# Propulsion.net
KiCad netlist of a schematic drawn in Altium Designer
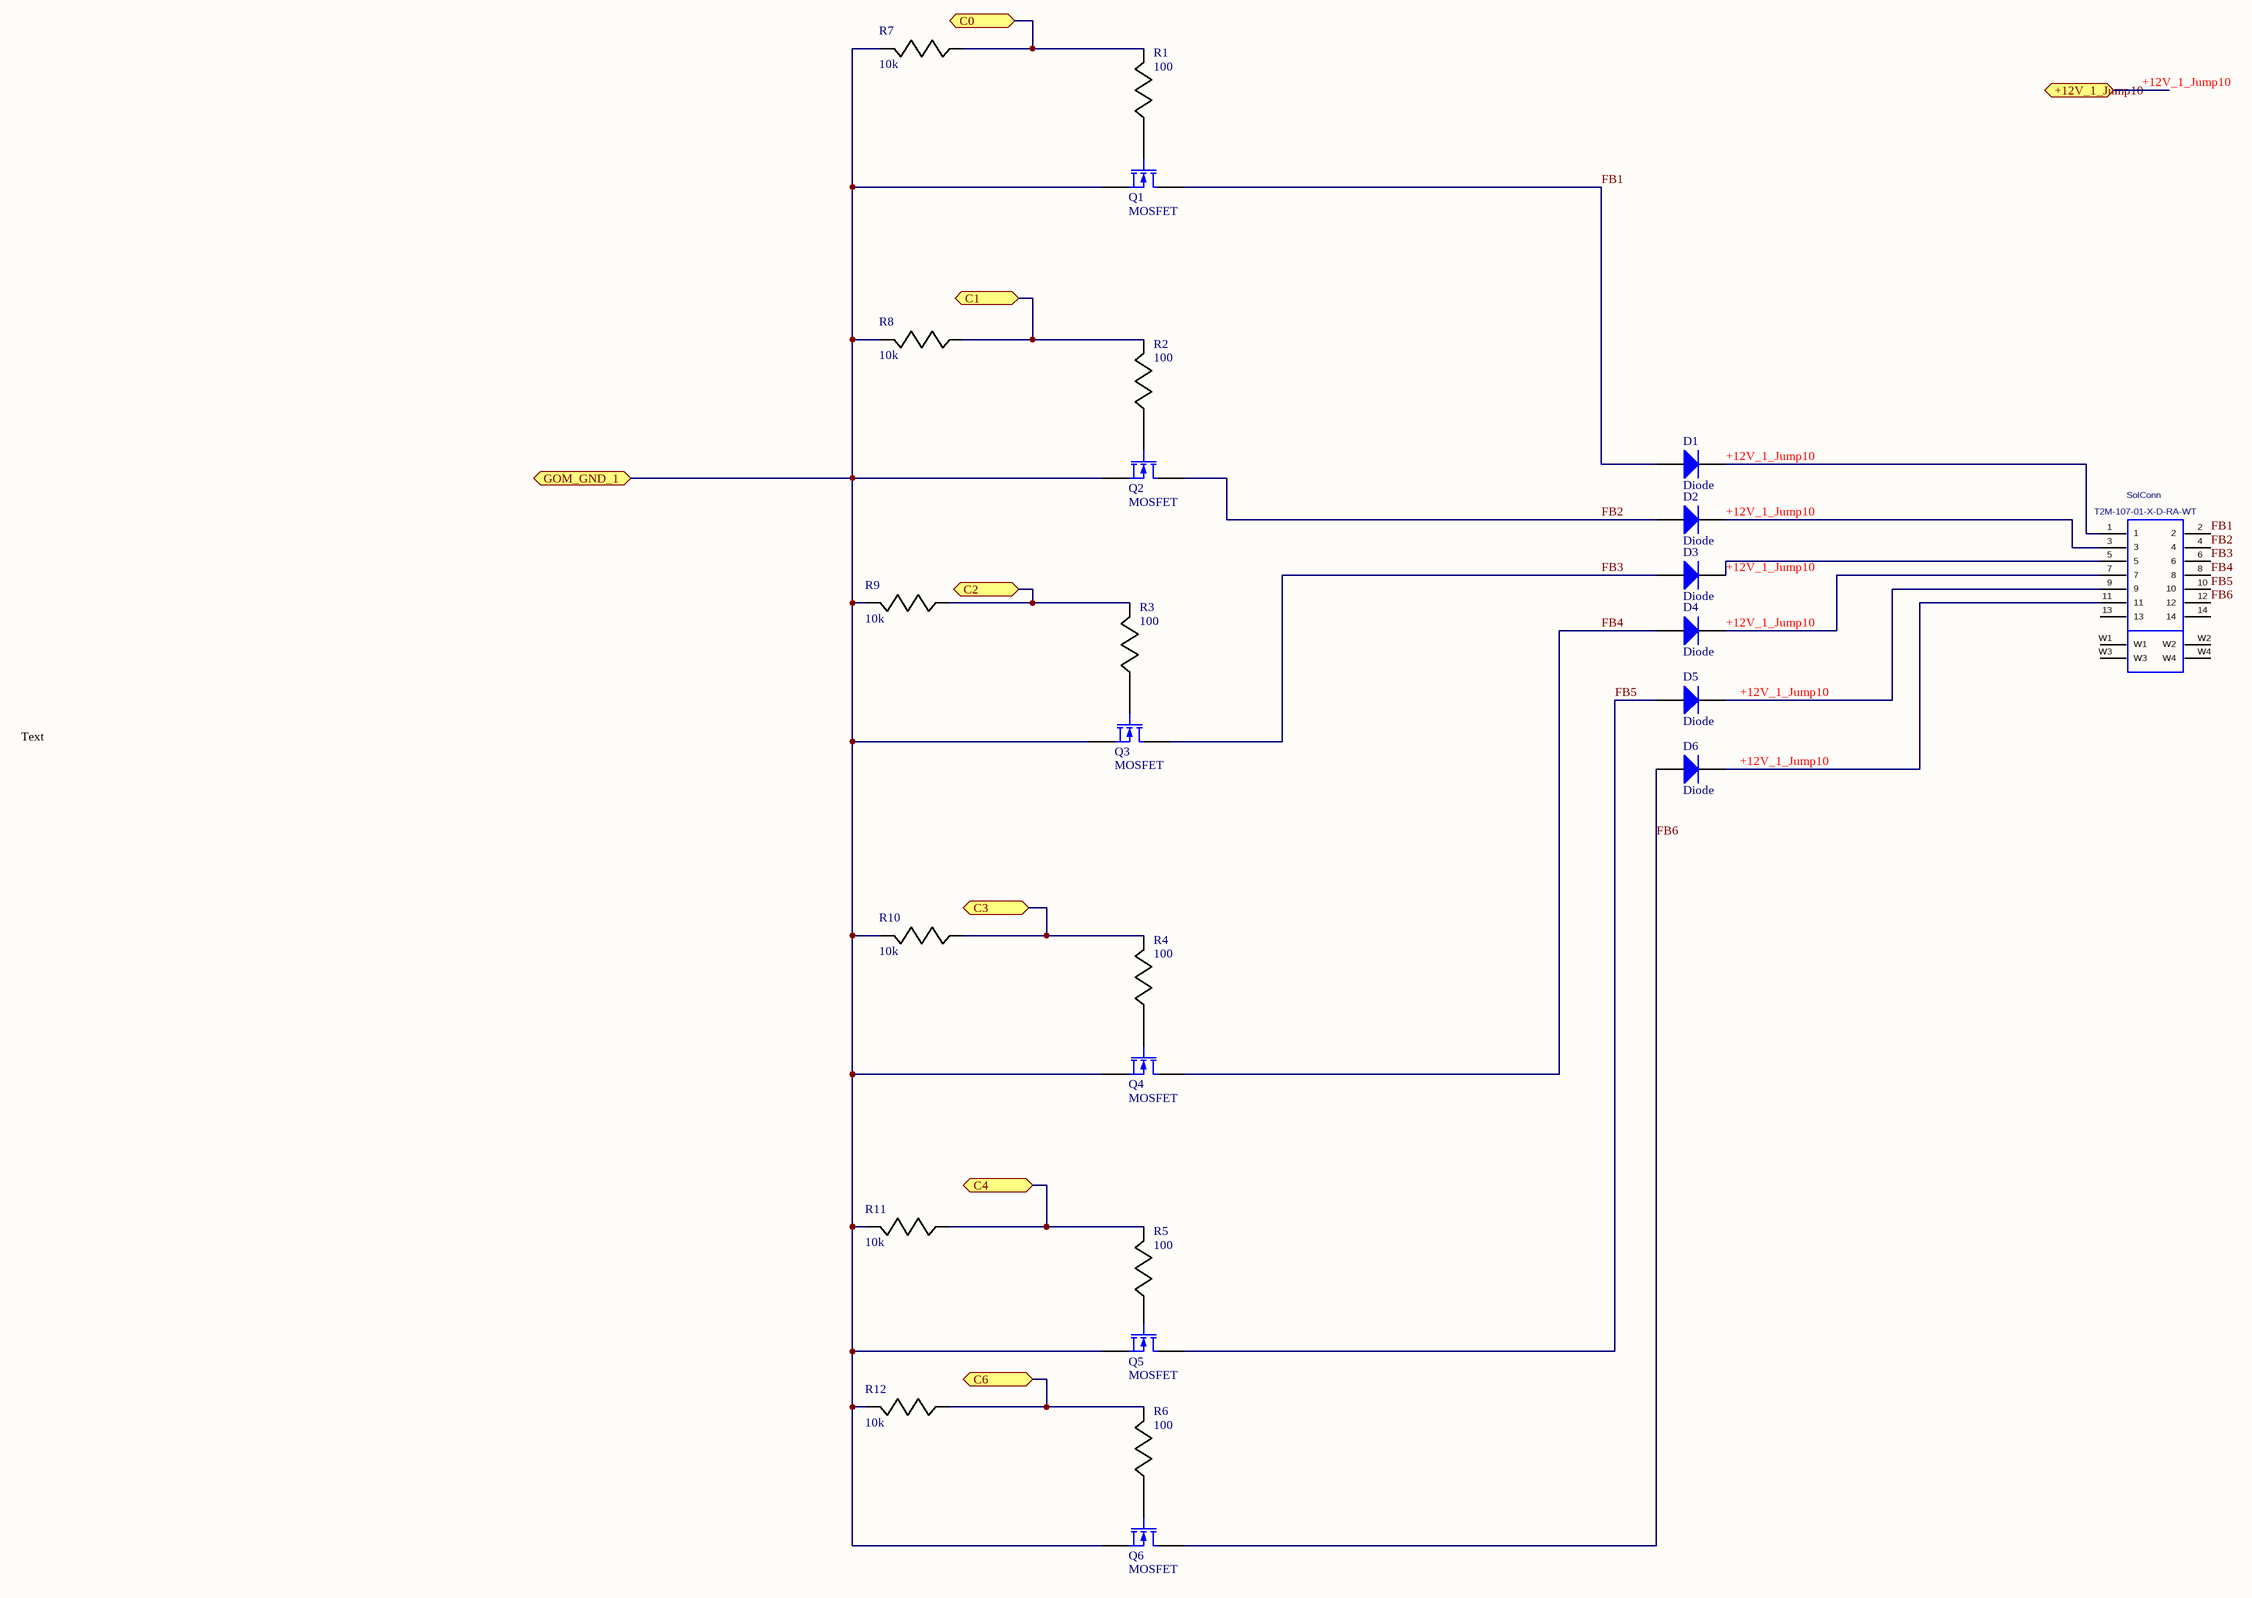
[diagram p0: Propulsion.SchDoc]

(export (version "E")
  (design (tool "Eeschema 10.0.6"))
  (components
    (comp (ref "D1")
      (value "Diode")
      (footprint "SMC")
      (description "Default Diode")
      (fields (field (name "PUBLISHER") "Altium Limited"))
      (libsource (lib "Miscellaneous Devices") (part "Diode"))
    )
    (comp (ref "D2")
      (value "Diode")
      (footprint "SMC")
      (description "Default Diode")
      (fields (field (name "PUBLISHER") "Altium Limited"))
      (libsource (lib "Miscellaneous Devices") (part "Diode"))
    )
    (comp (ref "D3")
      (value "Diode")
      (footprint "SMC")
      (description "Default Diode")
      (fields (field (name "PUBLISHER") "Altium Limited"))
      (libsource (lib "Miscellaneous Devices") (part "Diode"))
    )
    (comp (ref "D4")
      (value "Diode")
      (footprint "SMC")
      (description "Default Diode")
      (fields (field (name "PUBLISHER") "Altium Limited"))
      (libsource (lib "Miscellaneous Devices") (part "Diode"))
    )
    (comp (ref "D5")
      (value "Diode")
      (footprint "SMC")
      (description "Default Diode")
      (fields (field (name "PUBLISHER") "Altium Limited"))
      (libsource (lib "Miscellaneous Devices") (part "Diode"))
    )
    (comp (ref "D6")
      (value "Diode")
      (footprint "SMC")
      (description "Default Diode")
      (fields (field (name "PUBLISHER") "Altium Limited"))
      (libsource (lib "Miscellaneous Devices") (part "Diode"))
    )
    (comp (ref "Q1")
      (value "MOSFET")
      (footprint "TO-226-AA")
      (description "N-Channel MOSFET")
      (fields (field (name "PUBLISHER") "Altium Limited"))
      (libsource (lib "Miscellaneous Devices") (part "MOSFET-N"))
    )
    (comp (ref "Q2")
      (value "MOSFET")
      (footprint "TO-226-AA")
      (description "N-Channel MOSFET")
      (fields (field (name "PUBLISHER") "Altium Limited"))
      (libsource (lib "Miscellaneous Devices") (part "MOSFET-N"))
    )
    (comp (ref "Q3")
      (value "MOSFET")
      (footprint "TO-226-AA")
      (description "N-Channel MOSFET")
      (fields (field (name "PUBLISHER") "Altium Limited"))
      (libsource (lib "Miscellaneous Devices") (part "MOSFET-N"))
    )
    (comp (ref "Q4")
      (value "MOSFET")
      (footprint "TO-226-AA")
      (description "N-Channel MOSFET")
      (fields (field (name "PUBLISHER") "Altium Limited"))
      (libsource (lib "Miscellaneous Devices") (part "MOSFET-N"))
    )
    (comp (ref "Q5")
      (value "MOSFET")
      (footprint "TO-226-AA")
      (description "N-Channel MOSFET")
      (fields (field (name "PUBLISHER") "Altium Limited"))
      (libsource (lib "Miscellaneous Devices") (part "MOSFET-N"))
    )
    (comp (ref "Q6")
      (value "MOSFET")
      (footprint "TO-226-AA")
      (description "N-Channel MOSFET")
      (fields (field (name "PUBLISHER") "Altium Limited"))
      (libsource (lib "Miscellaneous Devices") (part "MOSFET-N"))
    )
    (comp (ref "R1")
      (value "100")
      (footprint "AXIAL-0.3")
      (description "Imported")
      (fields (field (name "MANUFACTURER_PART_NUMBER") "PMR100HZPFU6L00"))
      (libsource (lib "2016-03-26_18-23-46") (part "PMR100HZPFU6L00"))
    )
    (comp (ref "R2")
      (value "100")
      (footprint "AXIAL-0.3")
      (description "Imported")
      (fields (field (name "MANUFACTURER_PART_NUMBER") "PMR100HZPFU6L00"))
      (libsource (lib "2016-03-26_18-23-46") (part "PMR100HZPFU6L00"))
    )
    (comp (ref "R3")
      (value "100")
      (footprint "AXIAL-0.3")
      (description "Imported")
      (fields (field (name "MANUFACTURER_PART_NUMBER") "PMR100HZPFU6L00"))
      (libsource (lib "2016-03-26_18-23-46") (part "PMR100HZPFU6L00"))
    )
    (comp (ref "R4")
      (value "100")
      (footprint "AXIAL-0.3")
      (description "Imported")
      (fields (field (name "MANUFACTURER_PART_NUMBER") "PMR100HZPFU6L00"))
      (libsource (lib "2016-03-26_18-23-46") (part "PMR100HZPFU6L00"))
    )
    (comp (ref "R5")
      (value "100")
      (footprint "AXIAL-0.3")
      (description "Imported")
      (fields (field (name "MANUFACTURER_PART_NUMBER") "PMR100HZPFU6L00"))
      (libsource (lib "2016-03-26_18-23-46") (part "PMR100HZPFU6L00"))
    )
    (comp (ref "R6")
      (value "100")
      (footprint "AXIAL-0.3")
      (description "Imported")
      (fields (field (name "MANUFACTURER_PART_NUMBER") "PMR100HZPFU6L00"))
      (libsource (lib "2016-03-26_18-23-46") (part "PMR100HZPFU6L00"))
    )
    (comp (ref "R7")
      (value "10k")
      (footprint "AXIAL-0.3")
      (description "Imported")
      (fields (field (name "MANUFACTURER_PART_NUMBER") "PMR100HZPFU6L00"))
      (libsource (lib "2016-03-26_18-23-46") (part "PMR100HZPFU6L00"))
    )
    (comp (ref "R8")
      (value "10k")
      (footprint "AXIAL-0.3")
      (description "Imported")
      (fields (field (name "MANUFACTURER_PART_NUMBER") "PMR100HZPFU6L00"))
      (libsource (lib "2016-03-26_18-23-46") (part "PMR100HZPFU6L00"))
    )
    (comp (ref "R9")
      (value "10k")
      (footprint "AXIAL-0.3")
      (description "Imported")
      (fields (field (name "MANUFACTURER_PART_NUMBER") "PMR100HZPFU6L00"))
      (libsource (lib "2016-03-26_18-23-46") (part "PMR100HZPFU6L00"))
    )
    (comp (ref "R10")
      (value "10k")
      (footprint "AXIAL-0.3")
      (description "Imported")
      (fields (field (name "MANUFACTURER_PART_NUMBER") "PMR100HZPFU6L00"))
      (libsource (lib "2016-03-26_18-23-46") (part "PMR100HZPFU6L00"))
    )
    (comp (ref "R11")
      (value "10k")
      (footprint "AXIAL-0.3")
      (description "Imported")
      (fields (field (name "MANUFACTURER_PART_NUMBER") "PMR100HZPFU6L00"))
      (libsource (lib "2016-03-26_18-23-46") (part "PMR100HZPFU6L00"))
    )
    (comp (ref "R12")
      (value "10k")
      (footprint "AXIAL-0.3")
      (description "Imported")
      (fields (field (name "MANUFACTURER_PART_NUMBER") "PMR100HZPFU6L00"))
      (libsource (lib "2016-03-26_18-23-46") (part "PMR100HZPFU6L00"))
    )
    (comp (ref "SolConn")
      (value "T2M-107-01-X-D-RA-WT")
      (footprint "T2M-107-01-X-D-RA-WT")
      (description "2MM PITCH SHROUDED RIGHT ANGLE TERMINAL STRIP.")
      (fields
        (field (name "MANUFACTURER") "SAMTEC")
        (field (name "CREATED") "September 24, 2014 - Wendy Xin")
      )
      (libsource (lib "T2M-107-01-X-D-RA-WT") (part "T2M-107-01-X-D-RA-WT"))
    )
  )
  (nets
    (net (code "1") (name "/+12V_1_Jump10") (class "Default")
      (node (ref "D1") (pin "2") (pinfunction "K_2") (pintype "passive"))
      (node (ref "D2") (pin "2") (pinfunction "K_2") (pintype "passive"))
      (node (ref "D3") (pin "2") (pinfunction "K_2") (pintype "passive"))
      (node (ref "D4") (pin "2") (pinfunction "K_2") (pintype "passive"))
      (node (ref "D5") (pin "2") (pinfunction "K_2") (pintype "passive"))
      (node (ref "D6") (pin "2") (pinfunction "K_2") (pintype "passive"))
      (node (ref "SolConn") (pin "1") (pinfunction "1_1") (pintype "passive"))
      (node (ref "SolConn") (pin "11") (pinfunction "11_11") (pintype "passive"))
      (node (ref "SolConn") (pin "3") (pinfunction "3_3") (pintype "passive"))
      (node (ref "SolConn") (pin "5") (pinfunction "5_5") (pintype "passive"))
      (node (ref "SolConn") (pin "7") (pinfunction "7_7") (pintype "passive"))
      (node (ref "SolConn") (pin "9") (pinfunction "9_9") (pintype "passive"))
    )
    (net (code "2") (name "/C0") (class "Default")
      (node (ref "R1") (pin "1") (pinfunction "1_1") (pintype "passive"))
      (node (ref "R7") (pin "2") (pinfunction "2_2") (pintype "passive"))
    )
    (net (code "3") (name "/C1") (class "Default")
      (node (ref "R2") (pin "1") (pinfunction "1_1") (pintype "passive"))
      (node (ref "R8") (pin "2") (pinfunction "2_2") (pintype "passive"))
    )
    (net (code "4") (name "/C2") (class "Default")
      (node (ref "R3") (pin "1") (pinfunction "1_1") (pintype "passive"))
      (node (ref "R9") (pin "2") (pinfunction "2_2") (pintype "passive"))
    )
    (net (code "5") (name "/C3") (class "Default")
      (node (ref "R10") (pin "2") (pinfunction "2_2") (pintype "passive"))
      (node (ref "R4") (pin "1") (pinfunction "1_1") (pintype "passive"))
    )
    (net (code "6") (name "/C4") (class "Default")
      (node (ref "R11") (pin "2") (pinfunction "2_2") (pintype "passive"))
      (node (ref "R5") (pin "1") (pinfunction "1_1") (pintype "passive"))
    )
    (net (code "7") (name "/C6") (class "Default")
      (node (ref "R12") (pin "2") (pinfunction "2_2") (pintype "passive"))
      (node (ref "R6") (pin "1") (pinfunction "1_1") (pintype "passive"))
    )
    (net (code "8") (name "/FB1") (class "Default")
      (node (ref "D1") (pin "1") (pinfunction "A_1") (pintype "passive"))
      (node (ref "Q1") (pin "1") (pinfunction "D_1") (pintype "passive"))
      (node (ref "SolConn") (pin "2") (pinfunction "2_2") (pintype "passive"))
    )
    (net (code "9") (name "/FB2") (class "Default")
      (node (ref "D2") (pin "1") (pinfunction "A_1") (pintype "passive"))
      (node (ref "Q2") (pin "1") (pinfunction "D_1") (pintype "passive"))
      (node (ref "SolConn") (pin "4") (pinfunction "4_4") (pintype "passive"))
    )
    (net (code "10") (name "/FB3") (class "Default")
      (node (ref "D3") (pin "1") (pinfunction "A_1") (pintype "passive"))
      (node (ref "Q3") (pin "1") (pinfunction "D_1") (pintype "passive"))
      (node (ref "SolConn") (pin "6") (pinfunction "6_6") (pintype "passive"))
    )
    (net (code "11") (name "/FB4") (class "Default")
      (node (ref "D4") (pin "1") (pinfunction "A_1") (pintype "passive"))
      (node (ref "Q4") (pin "1") (pinfunction "D_1") (pintype "passive"))
      (node (ref "SolConn") (pin "8") (pinfunction "8_8") (pintype "passive"))
    )
    (net (code "12") (name "/FB5") (class "Default")
      (node (ref "D5") (pin "1") (pinfunction "A_1") (pintype "passive"))
      (node (ref "Q5") (pin "1") (pinfunction "D_1") (pintype "passive"))
      (node (ref "SolConn") (pin "10") (pinfunction "10_10") (pintype "passive"))
    )
    (net (code "13") (name "/FB6") (class "Default")
      (node (ref "D6") (pin "1") (pinfunction "A_1") (pintype "passive"))
      (node (ref "Q6") (pin "1") (pinfunction "D_1") (pintype "passive"))
      (node (ref "SolConn") (pin "12") (pinfunction "12_12") (pintype "passive"))
    )
    (net (code "14") (name "/GOM_GND_1") (class "Default")
      (node (ref "Q1") (pin "3") (pinfunction "S_3") (pintype "passive"))
      (node (ref "Q2") (pin "3") (pinfunction "S_3") (pintype "passive"))
      (node (ref "Q3") (pin "3") (pinfunction "S_3") (pintype "passive"))
      (node (ref "Q4") (pin "3") (pinfunction "S_3") (pintype "passive"))
      (node (ref "Q5") (pin "3") (pinfunction "S_3") (pintype "passive"))
      (node (ref "Q6") (pin "3") (pinfunction "S_3") (pintype "passive"))
      (node (ref "R10") (pin "1") (pinfunction "1_1") (pintype "passive"))
      (node (ref "R11") (pin "1") (pinfunction "1_1") (pintype "passive"))
      (node (ref "R12") (pin "1") (pinfunction "1_1") (pintype "passive"))
      (node (ref "R7") (pin "1") (pinfunction "1_1") (pintype "passive"))
      (node (ref "R8") (pin "1") (pinfunction "1_1") (pintype "passive"))
      (node (ref "R9") (pin "1") (pinfunction "1_1") (pintype "passive"))
    )
    (net (code "15") (name "Net-(Q1-G)") (class "Default")
      (node (ref "Q1") (pin "2") (pinfunction "G_2") (pintype "passive"))
      (node (ref "R1") (pin "2") (pinfunction "2_2") (pintype "passive"))
    )
    (net (code "16") (name "Net-(Q2-G)") (class "Default")
      (node (ref "Q2") (pin "2") (pinfunction "G_2") (pintype "passive"))
      (node (ref "R2") (pin "2") (pinfunction "2_2") (pintype "passive"))
    )
    (net (code "17") (name "Net-(Q3-G)") (class "Default")
      (node (ref "Q3") (pin "2") (pinfunction "G_2") (pintype "passive"))
      (node (ref "R3") (pin "2") (pinfunction "2_2") (pintype "passive"))
    )
    (net (code "18") (name "Net-(Q4-G)") (class "Default")
      (node (ref "Q4") (pin "2") (pinfunction "G_2") (pintype "passive"))
      (node (ref "R4") (pin "2") (pinfunction "2_2") (pintype "passive"))
    )
    (net (code "19") (name "Net-(Q6-G)") (class "Default")
      (node (ref "Q6") (pin "2") (pinfunction "G_2") (pintype "passive"))
      (node (ref "R6") (pin "2") (pinfunction "2_2") (pintype "passive"))
    )
    (net (code "20") (name "unconnected-(Q5-G-Pad2)") (class "Default")
      (node (ref "Q5") (pin "2") (pinfunction "G_2") (pintype "passive"))
    )
    (net (code "21") (name "unconnected-(R5-Pad2)") (class "Default")
      (node (ref "R5") (pin "2") (pinfunction "2_2") (pintype "passive"))
    )
    (net (code "22") (name "unconnected-(SolConn-Pad13)") (class "Default")
      (node (ref "SolConn") (pin "13") (pinfunction "13_13") (pintype "passive"))
    )
    (net (code "23") (name "unconnected-(SolConn-Pad14)") (class "Default")
      (node (ref "SolConn") (pin "14") (pinfunction "14_14") (pintype "passive"))
    )
    (net (code "24") (name "unconnected-(SolConn-PadW1)") (class "Default")
      (node (ref "SolConn") (pin "W1") (pinfunction "W1_W1") (pintype "passive"))
    )
    (net (code "25") (name "unconnected-(SolConn-PadW2)") (class "Default")
      (node (ref "SolConn") (pin "W2") (pinfunction "W2_W2") (pintype "passive"))
    )
    (net (code "26") (name "unconnected-(SolConn-PadW3)") (class "Default")
      (node (ref "SolConn") (pin "W3") (pinfunction "W3_W3") (pintype "passive"))
    )
    (net (code "27") (name "unconnected-(SolConn-PadW4)") (class "Default")
      (node (ref "SolConn") (pin "W4") (pinfunction "W4_W4") (pintype "passive"))
    )
  )
)
